# Guide_laser.net
KiCad netlist of a schematic drawn in Altium Designer
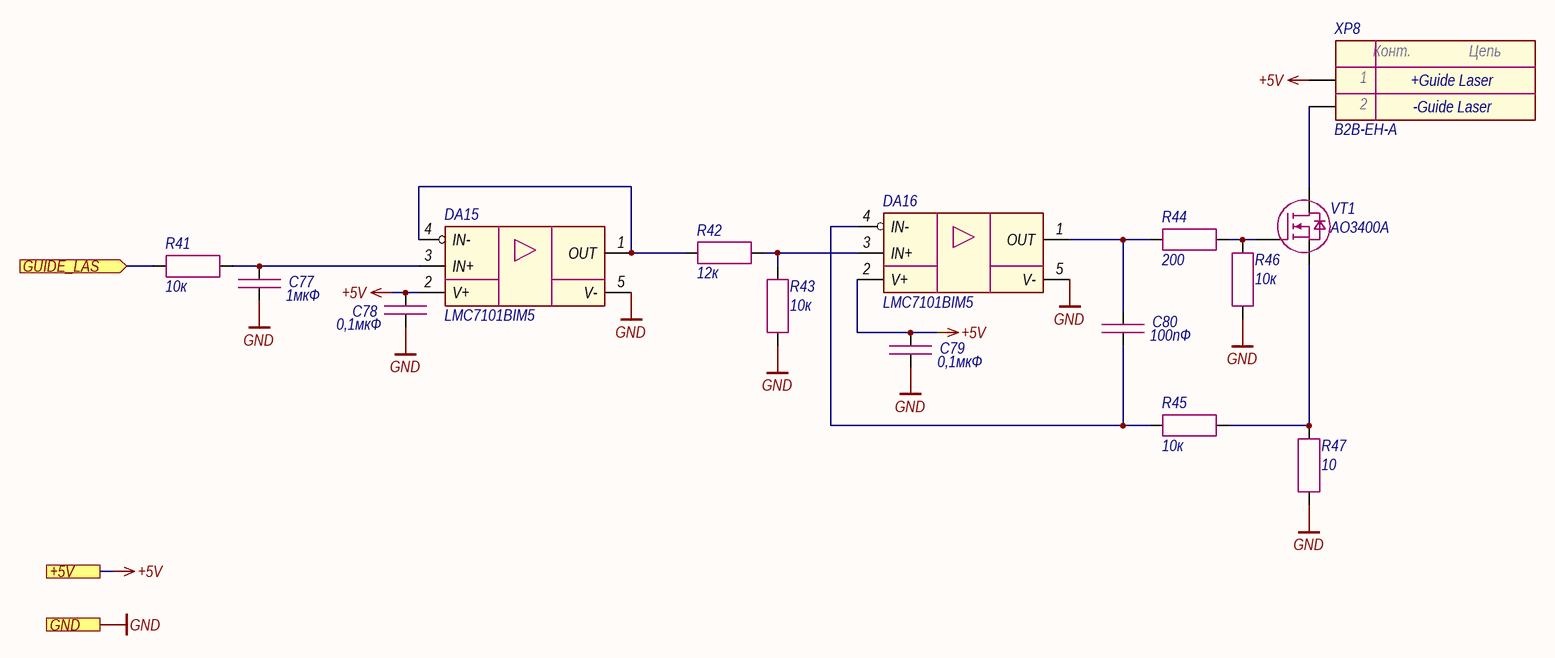
[diagram p0: Guide_laser.SchDoc]

(export (version "E")
  (design (tool "Eeschema 10.0.6"))
  (components
    (comp (ref "C77")
      (value "1мкФ")
      (footprint "Pcb_library:CAP_0603")
      (fields (field (name "MANUFACTURER") "Murata"))
      (libsource (lib "Schem_library") (part "Capacitor"))
    )
    (comp (ref "C78")
      (value "0,1мкФ")
      (footprint "Pcb_library:CAP_0603")
      (fields (field (name "MANUFACTURER") "Murata"))
      (libsource (lib "Schem_library") (part "Capacitor"))
    )
    (comp (ref "C79")
      (value "0,1мкФ")
      (footprint "Pcb_library:CAP_0603")
      (fields (field (name "MANUFACTURER") "Murata"))
      (libsource (lib "Schem_library") (part "Capacitor"))
    )
    (comp (ref "C80")
      (value "100пФ")
      (footprint "Pcb_library:CAP_0603")
      (fields (field (name "MANUFACTURER") "Murata"))
      (libsource (lib "Schem_library") (part "Capacitor"))
    )
    (comp (ref "DA15")
      (value "LMC7101BIM5")
      (footprint "Pcb_library:SOT-23-5")
      (fields (field (name "MANUFACTURER") "Texas Instruments"))
      (libsource (lib "Schem_library") (part "LMC7101"))
    )
    (comp (ref "DA16")
      (value "LMC7101BIM5")
      (footprint "Pcb_library:SOT-23-5")
      (fields (field (name "MANUFACTURER") "Texas Instruments"))
      (libsource (lib "Schem_library") (part "LMC7101"))
    )
    (comp (ref "R41")
      (value "10к")
      (footprint "Pcb_library:RES_0603")
      (fields (field (name "MANUFACTURER") "Yageo"))
      (libsource (lib "Schem_library") (part "Resistor"))
    )
    (comp (ref "R42")
      (value "12к")
      (footprint "Pcb_library:RES_0603")
      (fields (field (name "MANUFACTURER") "Yageo"))
      (libsource (lib "Schem_library") (part "Resistor"))
    )
    (comp (ref "R43")
      (value "10к")
      (footprint "Pcb_library:RES_0603")
      (fields (field (name "MANUFACTURER") "Yageo"))
      (libsource (lib "Schem_library") (part "Resistor"))
    )
    (comp (ref "R44")
      (value "200")
      (footprint "Pcb_library:RES_0603")
      (fields (field (name "MANUFACTURER") "Yageo"))
      (libsource (lib "Schem_library") (part "Resistor"))
    )
    (comp (ref "R45")
      (value "10к")
      (footprint "Pcb_library:RES_0603")
      (fields (field (name "MANUFACTURER") "Yageo"))
      (libsource (lib "Schem_library") (part "Resistor"))
    )
    (comp (ref "R46")
      (value "10к")
      (footprint "Pcb_library:RES_0603")
      (fields (field (name "MANUFACTURER") "Yageo"))
      (libsource (lib "Schem_library") (part "Resistor"))
    )
    (comp (ref "R47")
      (value "10")
      (footprint "Pcb_library:RES_1210")
      (fields (field (name "MANUFACTURER") "Yageo"))
      (libsource (lib "Schem_library") (part "Resistor"))
    )
    (comp (ref "VT1")
      (value "AO3400A")
      (footprint "Pcb_library:SOT-23-3")
      (fields (field (name "MANUFACTURER") "UMW"))
      (libsource (lib "Schem_library") (part "MOSFET N-channel"))
    )
    (comp (ref "XP8")
      (value "B2B-EH-A")
      (footprint "Pcb_library:B2B-EH-A")
      (fields (field (name "MANUFACTURER") "JST"))
      (libsource (lib "Schem_library") (part "Connector-2"))
    )
  )
  (nets
    (net (code "1") (name "+5V") (class "Default")
      (node (ref "C78") (pin "1") (pinfunction "1_1") (pintype "passive"))
      (node (ref "C79") (pin "1") (pinfunction "1_1") (pintype "passive"))
      (node (ref "DA15") (pin "2") (pinfunction "V+_2") (pintype "passive"))
      (node (ref "DA16") (pin "2") (pinfunction "V+_2") (pintype "passive"))
      (node (ref "XP8") (pin "1") (pintype "passive"))
    )
    (net (code "2") (name "/GUIDE_LAS") (class "Default")
      (node (ref "R41") (pin "1") (pinfunction "1_1") (pintype "passive"))
    )
    (net (code "3") (name "GND") (class "Default")
      (node (ref "C77") (pin "2") (pinfunction "2_2") (pintype "passive"))
      (node (ref "C78") (pin "2") (pinfunction "2_2") (pintype "passive"))
      (node (ref "C79") (pin "2") (pinfunction "2_2") (pintype "passive"))
      (node (ref "DA15") (pin "5") (pinfunction "V-_5") (pintype "passive"))
      (node (ref "DA16") (pin "5") (pinfunction "V-_5") (pintype "passive"))
      (node (ref "R43") (pin "2") (pinfunction "2_2") (pintype "passive"))
      (node (ref "R46") (pin "1") (pinfunction "1_1") (pintype "passive"))
      (node (ref "R47") (pin "1") (pinfunction "1_1") (pintype "passive"))
    )
    (net (code "4") (name "Net-(DA15-IN+)") (class "Default")
      (node (ref "C77") (pin "1") (pinfunction "1_1") (pintype "passive"))
      (node (ref "DA15") (pin "3") (pinfunction "IN+_3") (pintype "passive"))
      (node (ref "R41") (pin "2") (pinfunction "2_2") (pintype "passive"))
    )
    (net (code "5") (name "Net-(DA15-IN-)") (class "Default")
      (node (ref "DA15") (pin "1") (pinfunction "OUT_1") (pintype "passive"))
      (node (ref "DA15") (pin "4") (pinfunction "IN-_4") (pintype "passive"))
      (node (ref "R42") (pin "1") (pinfunction "1_1") (pintype "passive"))
    )
    (net (code "6") (name "Net-(DA16-IN+)") (class "Default")
      (node (ref "DA16") (pin "3") (pinfunction "IN+_3") (pintype "passive"))
      (node (ref "R42") (pin "2") (pinfunction "2_2") (pintype "passive"))
      (node (ref "R43") (pin "1") (pinfunction "1_1") (pintype "passive"))
    )
    (net (code "7") (name "Net-(DA16-IN-)") (class "Default")
      (node (ref "C80") (pin "2") (pinfunction "2_2") (pintype "passive"))
      (node (ref "DA16") (pin "4") (pinfunction "IN-_4") (pintype "passive"))
      (node (ref "R45") (pin "1") (pinfunction "1_1") (pintype "passive"))
    )
    (net (code "8") (name "Net-(DA16-OUT)") (class "Default")
      (node (ref "C80") (pin "1") (pinfunction "1_1") (pintype "passive"))
      (node (ref "DA16") (pin "1") (pinfunction "OUT_1") (pintype "passive"))
      (node (ref "R44") (pin "1") (pinfunction "1_1") (pintype "passive"))
    )
    (net (code "9") (name "Net-(VT1-D)") (class "Default")
      (node (ref "VT1") (pin "3") (pinfunction "D_3") (pintype "passive"))
      (node (ref "XP8") (pin "2") (pintype "passive"))
    )
    (net (code "10") (name "Net-(VT1-G)") (class "Default")
      (node (ref "R44") (pin "2") (pinfunction "2_2") (pintype "passive"))
      (node (ref "R46") (pin "2") (pinfunction "2_2") (pintype "passive"))
      (node (ref "VT1") (pin "1") (pinfunction "G_1") (pintype "passive"))
    )
    (net (code "11") (name "Net-(VT1-S)") (class "Default")
      (node (ref "R45") (pin "2") (pinfunction "2_2") (pintype "passive"))
      (node (ref "R47") (pin "2") (pinfunction "2_2") (pintype "passive"))
      (node (ref "VT1") (pin "2") (pinfunction "S_2") (pintype "passive"))
    )
  )
)
